# PLL_Counter.net
KiCad netlist of a schematic drawn in EAGLE
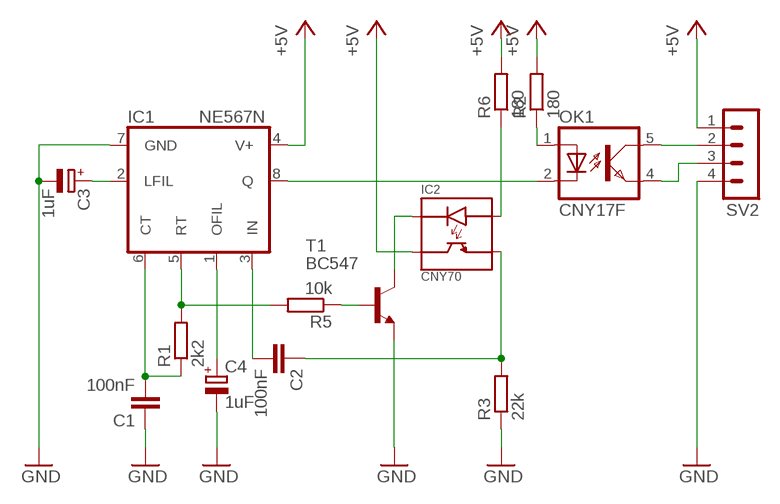
[diagram p0: schematic, sheet 1]

(export (version "E")
  (design (tool "Eeschema 10.0.6"))
  (components
    (comp (ref "C1")
      (value "100nF")
      (footprint "eagle-import:C025-025X050")
      (libsource (lib "eagle-import") (part "C-EU025-025X050"))
    )
    (comp (ref "C2")
      (value "100nF")
      (footprint "eagle-import:C025-025X050")
      (libsource (lib "eagle-import") (part "C-EU025-025X050"))
    )
    (comp (ref "C3")
      (value "1uF")
      (footprint "eagle-import:E2,5-5")
      (libsource (lib "eagle-import") (part "CPOL-EUE2.5-5"))
    )
    (comp (ref "C4")
      (value "1uF")
      (footprint "eagle-import:E2,5-5")
      (libsource (lib "eagle-import") (part "CPOL-EUE2.5-5"))
    )
    (comp (ref "IC1")
      (value "NE567N")
      (footprint "eagle-import:DIL08")
      (libsource (lib "eagle-import") (part "567NNE"))
    )
    (comp (ref "IC2")
      (value "CNY70")
      (footprint "eagle-import:CNY70")
      (libsource (lib "eagle-import") (part "CNY70"))
    )
    (comp (ref "OK1")
      (value "CNY17F")
      (footprint "eagle-import:DIL06")
      (fields (field (name "MF") "VISHAY/TELEFUNKEN") (field (name "MPN") "CNY17F-3"))
      (libsource (lib "eagle-import") (part "CNY17F"))
    )
    (comp (ref "R1")
      (value "2k2")
      (footprint "eagle-import:0204_7")
      (libsource (lib "eagle-import") (part "R-EU_0204/7"))
    )
    (comp (ref "R2")
      (value "180")
      (footprint "eagle-import:0204_7")
      (libsource (lib "eagle-import") (part "R-EU_0204/7"))
    )
    (comp (ref "R3")
      (value "22k")
      (footprint "eagle-import:0204_7")
      (libsource (lib "eagle-import") (part "R-EU_0204/7"))
    )
    (comp (ref "R5")
      (value "10k")
      (footprint "eagle-import:0204_7")
      (libsource (lib "eagle-import") (part "R-EU_0204/7"))
    )
    (comp (ref "R6")
      (value "180")
      (footprint "eagle-import:0204_7")
      (libsource (lib "eagle-import") (part "R-EU_0204/7"))
    )
    (comp (ref "SV2")
      (value "MA04-1")
      (footprint "eagle-import:MA04-1")
      (libsource (lib "eagle-import") (part "MA04-1"))
    )
    (comp (ref "T1")
      (value "BC547")
      (footprint "eagle-import:TO92")
      (libsource (lib "eagle-import") (part "BC547"))
    )
  )
  (nets
    (net (code "1") (name "+5V") (class "Default")
      (node (ref "IC1") (pin "4") (pinfunction "V+_4") (pintype "power_in"))
      (node (ref "IC2") (pin "DC") (pinfunction "DC_DC") (pintype "bidirectional"))
      (node (ref "R2") (pin "2") (pinfunction "2_2") (pintype "passive"))
      (node (ref "R6") (pin "2") (pinfunction "2_2") (pintype "passive"))
      (node (ref "SV2") (pin "1") (pinfunction "1_1") (pintype "passive"))
    )
    (net (code "2") (name "GND") (class "Default")
      (node (ref "C1") (pin "1") (pinfunction "1_1") (pintype "passive"))
      (node (ref "C3") (pin "-") (pinfunction "-_-") (pintype "passive"))
      (node (ref "C4") (pin "-") (pinfunction "-_-") (pintype "passive"))
      (node (ref "IC1") (pin "7") (pinfunction "GND_7") (pintype "power_in"))
      (node (ref "R3") (pin "1") (pinfunction "1_1") (pintype "passive"))
      (node (ref "SV2") (pin "4") (pinfunction "4_4") (pintype "passive"))
      (node (ref "T1") (pin "1") (pinfunction "E_1") (pintype "passive"))
    )
    (net (code "3") (name "Net-(C2-Pad1)") (class "Default")
      (node (ref "C2") (pin "1") (pinfunction "1_1") (pintype "passive"))
      (node (ref "IC2") (pin "DE") (pinfunction "DE_DE") (pintype "bidirectional"))
      (node (ref "R3") (pin "2") (pinfunction "2_2") (pintype "passive"))
    )
    (net (code "4") (name "Net-(IC1-CT)") (class "Default")
      (node (ref "C1") (pin "2") (pinfunction "2_2") (pintype "passive"))
      (node (ref "IC1") (pin "6") (pinfunction "CT_6") (pintype "passive"))
      (node (ref "R1") (pin "1") (pinfunction "1_1") (pintype "passive"))
    )
    (net (code "5") (name "Net-(IC1-IN)") (class "Default")
      (node (ref "C2") (pin "2") (pinfunction "2_2") (pintype "passive"))
      (node (ref "IC1") (pin "3") (pinfunction "IN_3") (pintype "input"))
    )
    (net (code "6") (name "Net-(IC1-LFIL)") (class "Default")
      (node (ref "C3") (pin "+") (pinfunction "+_+") (pintype "passive"))
      (node (ref "IC1") (pin "2") (pinfunction "LFIL_2") (pintype "passive"))
    )
    (net (code "7") (name "Net-(IC1-OFIL)") (class "Default")
      (node (ref "C4") (pin "+") (pinfunction "+_+") (pintype "passive"))
      (node (ref "IC1") (pin "1") (pinfunction "OFIL_1") (pintype "output"))
    )
    (net (code "8") (name "Net-(IC1-Q)") (class "Default")
      (node (ref "IC1") (pin "8") (pinfunction "Q_8") (pintype "output"))
      (node (ref "OK1") (pin "2") (pinfunction "C_2") (pintype "passive"))
    )
    (net (code "9") (name "Net-(IC1-RT)") (class "Default")
      (node (ref "IC1") (pin "5") (pinfunction "RT_5") (pintype "passive"))
      (node (ref "R1") (pin "2") (pinfunction "2_2") (pintype "passive"))
      (node (ref "R5") (pin "2") (pinfunction "2_2") (pintype "passive"))
    )
    (net (code "10") (name "Net-(IC2-PadEA)") (class "Default")
      (node (ref "IC2") (pin "EA") (pinfunction "EA_EA") (pintype "bidirectional"))
      (node (ref "R6") (pin "1") (pinfunction "1_1") (pintype "passive"))
    )
    (net (code "11") (name "Net-(OK1-A)") (class "Default")
      (node (ref "OK1") (pin "1") (pinfunction "A_1") (pintype "passive"))
      (node (ref "R2") (pin "1") (pinfunction "1_1") (pintype "passive"))
    )
    (net (code "12") (name "Net-(OK1-COL)") (class "Default")
      (node (ref "OK1") (pin "5") (pinfunction "COL_5") (pintype "passive"))
      (node (ref "SV2") (pin "2") (pinfunction "2_2") (pintype "passive"))
    )
    (net (code "13") (name "Net-(OK1-EMIT)") (class "Default")
      (node (ref "OK1") (pin "4") (pinfunction "EMIT_4") (pintype "passive"))
      (node (ref "SV2") (pin "3") (pinfunction "3_3") (pintype "passive"))
    )
    (net (code "14") (name "Net-(T1-B)") (class "Default")
      (node (ref "R5") (pin "1") (pinfunction "1_1") (pintype "passive"))
      (node (ref "T1") (pin "2") (pinfunction "B_2") (pintype "passive"))
    )
    (net (code "15") (name "Net-(T1-C)") (class "Default")
      (node (ref "IC2") (pin "EK") (pinfunction "EK_EK") (pintype "bidirectional"))
      (node (ref "T1") (pin "3") (pinfunction "C_3") (pintype "passive"))
    )
  )
)
